# Relay_SPDT.net
KiCad netlist of a schematic drawn in Altium Designer
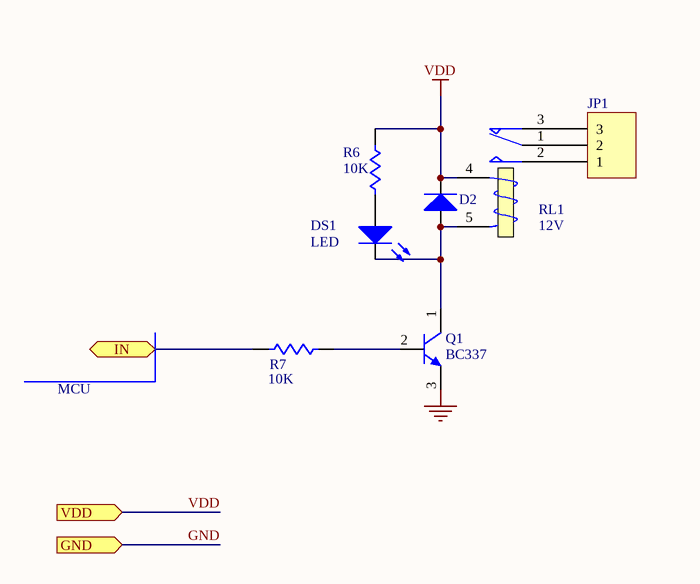
[diagram p0: Relay_SPDT.SchDoc]

(export (version "E")
  (design (tool "Eeschema 10.0.6"))
  (components
    (comp (ref "D2")
      (value "Diode")
      (footprint "DIODE-0.4")
      (description "Default Diode")
      (fields (field (name "MANUFACTURER") "Generic Components") (field (name "PUBLISHER") "Altium Limited"))
      (libsource (lib "Miscellaneous Devices") (part "Diode"))
    )
    (comp (ref "DS1")
      (value "LED")
      (footprint "LED-5mm_Red")
      (description "Typical INFRARED GaAs LED")
      (fields (field (name "MANUFACTURER") "Generic Components") (field (name "PUBLISHER") "Altium Limited"))
      (libsource (lib "Miscellaneous Devices") (part "LED"))
    )
    (comp (ref "JP1")
      (value "Header 3")
      (footprint "Fonics_3C")
      (description "Header, 3-Pin")
      (fields (field (name "MANUFACTURER") "Generic Components") (field (name "PUBLISHER") "Altium Limited"))
      (libsource (lib "Miscellaneous Connectors") (part "Header 3"))
    )
    (comp (ref "Q1")
      (value "BC337")
      (footprint "TO92C")
      (description "NPN Bipolar Transistor")
      (fields (field (name "MANUFACTURER") "Generic Components") (field (name "PUBLISHER") "Altium Limited"))
      (libsource (lib "Miscellaneous Devices") (part "NPN"))
    )
    (comp (ref "R6")
      (value "10K")
      (footprint "AXIAL-0.4")
      (description "Resistor")
      (fields
        (field (name "MANUFACTURER") "Generic Components")
        (field (name "Comment") "Res1")
        (field (name "PUBLISHER") "Altium Limited")
      )
      (libsource (lib "Miscellaneous Devices") (part "Res1"))
    )
    (comp (ref "R7")
      (value "10K")
      (footprint "AXIAL-0.4")
      (description "Resistor")
      (fields
        (field (name "MANUFACTURER") "Generic Components")
        (field (name "Comment") "Res1")
        (field (name "PUBLISHER") "Altium Limited")
      )
      (libsource (lib "Miscellaneous Devices") (part "Res1"))
    )
    (comp (ref "RL1")
      (value "12V")
      (footprint "RELAY-SPDT-1")
      (description "SPDT Relay")
      (fields
        (field (name "MANUFACTURER") "Generic Components")
        (field (name "Comment") "Relay-SPDT_2")
        (field (name "PUBLISHER") "Altium Limited")
      )
      (libsource (lib "Miscellaneous Devices") (part "Relay-SPDT_2"))
    )
  )
  (nets
    (net (code "1") (name "/IN") (class "Default")
      (node (ref "R7") (pin "2") (pinfunction "2_2") (pintype "passive"))
    )
    (net (code "2") (name "GND") (class "Default")
      (node (ref "Q1") (pin "3") (pinfunction "E_3") (pintype "passive"))
    )
    (net (code "3") (name "Net-(D2-A)") (class "Default")
      (node (ref "D2") (pin "1") (pinfunction "A_1") (pintype "passive"))
      (node (ref "DS1") (pin "2") (pinfunction "K_2") (pintype "passive"))
      (node (ref "Q1") (pin "1") (pinfunction "C_1") (pintype "passive"))
      (node (ref "RL1") (pin "5") (pinfunction "T2_5") (pintype "passive"))
    )
    (net (code "4") (name "Net-(DS1-A)") (class "Default")
      (node (ref "DS1") (pin "1") (pinfunction "A_1") (pintype "passive"))
      (node (ref "R6") (pin "2") (pinfunction "2_2") (pintype "passive"))
    )
    (net (code "5") (name "Net-(Q1-B)") (class "Default")
      (node (ref "Q1") (pin "2") (pinfunction "B_2") (pintype "passive"))
      (node (ref "R7") (pin "1") (pinfunction "1_1") (pintype "passive"))
    )
    (net (code "6") (name "Net-(RL1-COM)") (class "Default")
      (node (ref "JP1") (pin "2") (pinfunction "2_2") (pintype "passive"))
      (node (ref "RL1") (pin "1") (pinfunction "COM_1") (pintype "passive"))
    )
    (net (code "7") (name "Net-(RL1-NC)") (class "Default")
      (node (ref "JP1") (pin "3") (pinfunction "3_3") (pintype "passive"))
      (node (ref "RL1") (pin "3") (pinfunction "NC_3") (pintype "passive"))
    )
    (net (code "8") (name "Net-(RL1-NO)") (class "Default")
      (node (ref "JP1") (pin "1") (pinfunction "1_1") (pintype "passive"))
      (node (ref "RL1") (pin "2") (pinfunction "NO_2") (pintype "passive"))
    )
    (net (code "9") (name "VDD") (class "Default")
      (node (ref "D2") (pin "2") (pinfunction "K_2") (pintype "passive"))
      (node (ref "R6") (pin "1") (pinfunction "1_1") (pintype "passive"))
      (node (ref "RL1") (pin "4") (pinfunction "T1_4") (pintype "passive"))
    )
  )
)
